# BatteryMonitor.net
KiCad netlist of a schematic drawn in Altium Designer
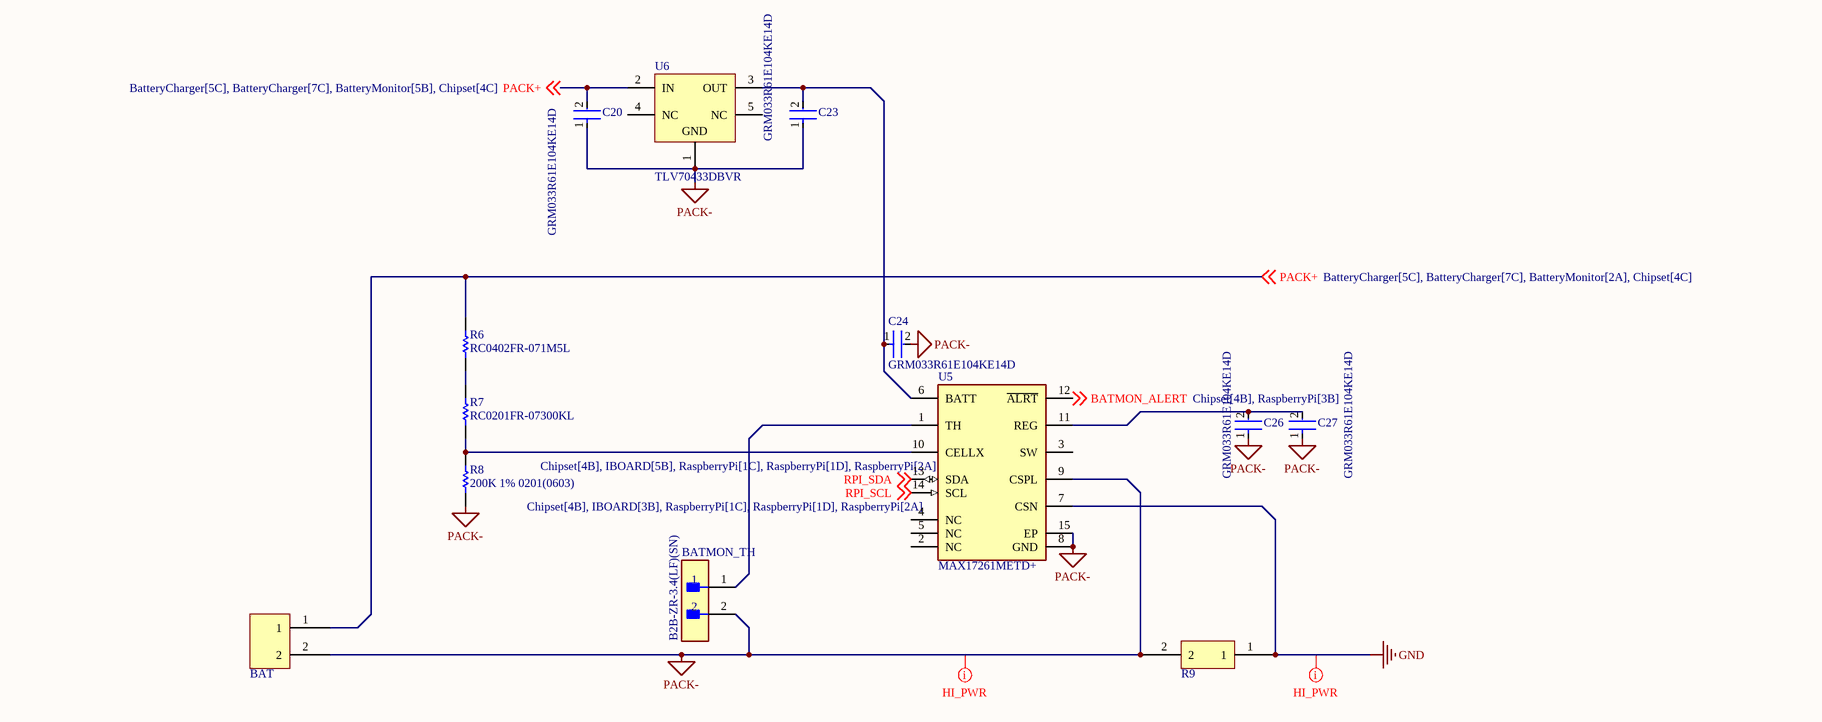
[diagram p0: BatteryMonitor.SchDoc]

(export (version "E")
  (design (tool "Eeschema 10.0.6"))
  (components
    (comp (ref "BAT")
      (value "WJ500V-5.08-2P")
      (footprint "WJ500V-5.08-2P")
      (libsource (lib "WJ500V-5.08-2P") (part "WJ500V-5.08-2P"))
    )
    (comp (ref "BATMON_TH")
      (value "B2B-ZR-3.4(LF)(SN)")
      (footprint "FP-B2B-ZR-3_4_LF_SN-MFG")
      (description "CONN HEADER VERT 2POS 1.5MM")
      (libsource (lib "Altium Content Vault") (part "3bc925449376181038e59eaffc5286c"))
    )
    (comp (ref "C20")
      (value "GRM033R61E104KE14D")
      (footprint "FP-GRM033-0_03-IPC_B")
      (description "Chip Multilayer Ceramic Capacitors for General Purpose, 0201, 0.10uF, X5R, 15%, 10%, 25V")
      (fields (field (name "TOLERANCE") "10%"))
      (libsource (lib "Altium Content Vault") (part "b4654b650e69147ec39a6b967a45e02"))
    )
    (comp (ref "C23")
      (value "GRM033R61E104KE14D")
      (footprint "FP-GRM033-0_03-IPC_B")
      (description "Chip Multilayer Ceramic Capacitors for General Purpose, 0201, 0.10uF, X5R, 15%, 10%, 25V")
      (fields (field (name "TOLERANCE") "10%"))
      (libsource (lib "Altium Content Vault") (part "b4654b650e69147ec39a6b967a45e02"))
    )
    (comp (ref "C24")
      (value "GRM033R61E104KE14D")
      (footprint "FP-GRM033-0_03-IPC_B")
      (description "Chip Multilayer Ceramic Capacitors for General Purpose, 0201, 0.10uF, X5R, 15%, 10%, 25V")
      (fields (field (name "TOLERANCE") "10%"))
      (libsource (lib "Altium Content Vault") (part "b4654b650e69147ec39a6b967a45e02"))
    )
    (comp (ref "C26")
      (value "GRM033R61E104KE14D")
      (footprint "FP-GRM033-0_03-IPC_B")
      (description "Chip Multilayer Ceramic Capacitors for General Purpose, 0201, 0.10uF, X5R, 15%, 10%, 25V")
      (fields (field (name "TOLERANCE") "10%"))
      (libsource (lib "Altium Content Vault") (part "b4654b650e69147ec39a6b967a45e02"))
    )
    (comp (ref "C27")
      (value "GRM033R61E104KE14D")
      (footprint "FP-GRM033-0_03-IPC_B")
      (description "Chip Multilayer Ceramic Capacitors for General Purpose, 0201, 0.10uF, X5R, 15%, 10%, 25V")
      (fields (field (name "TOLERANCE") "10%"))
      (libsource (lib "Altium Content Vault") (part "b4654b650e69147ec39a6b967a45e02"))
    )
    (comp (ref "R6")
      (value "RC0402FR-071M5L")
      (footprint "RESC1005X40X25NL05T10")
      (fields (field (name "MANUFACTURER") "Yageo / Phycomp"))
      (libsource (lib "Altium Content Vault") (part "RES"))
    )
    (comp (ref "R7")
      (value "RC0201FR-07300KL")
      (footprint "RESC0201(0603)_L")
      (description "300K 0.05W 1% 0201 (0603 Metric)  SMD")
      (fields (field (name "POWER") "0.05 W") (field (name "TOLERANCE") "1 %"))
      (libsource (lib "Altium Content Vault") (part "RES"))
    )
    (comp (ref "R8")
      (value "200K 1% 0201(0603)")
      (footprint "RESC0201(0603)_N")
      (description "200K 0.05W 1% 0201 (0603 Metric)  SMD")
      (fields (field (name "TOLERANCE") "1 %") (field (name "POWER") "0.05 W"))
      (libsource (lib "Altium Content Vault") (part "RES"))
    )
    (comp (ref "R9")
      (value "HoYLR2512-3W-10mR-1%")
      (footprint "HoYLR2512-3W-10mR-1%")
      (libsource (lib "HoYLR2512-3W-10mR-1%") (part "HoYLR2512-3W-10mR-1%"))
    )
    (comp (ref "U5")
      (value "MAX17261METD+")
      (footprint "FP-T1433-2C-MFG")
      (description "IC FUEL GAUGE LI+ M5 EZ 14TDFN")
      (fields
        (field (name "OCTOPART") "https://octopart.com/max17261metd%2B-maxim+integrated-91765041")
        (field (name "MANUFACTURER") "Maxim")
      )
      (libsource (lib "Altium Content Vault") (part "6a95d388af7a6271f6af8175f327b7b"))
    )
    (comp (ref "U6")
      (value "TLV70433DBVR")
      (footprint "DBV0005A_M")
      (fields (field (name "MANUFACTURER") "Texas Instruments"))
      (libsource (lib "Altium Content Vault") (part "TI-TLV704XXDBV5"))
    )
  )
  (nets
    (net (code "1") (name "BATMON_ALERT") (class "Default")
      (node (ref "U5") (pin "12") (pinfunction "~{ALRT}_12") (pintype "open_collector"))
    )
    (net (code "2") (name "GND") (class "Default")
      (node (ref "R9") (pin "1") (pinfunction "1_1") (pintype "passive"))
      (node (ref "U5") (pin "7") (pinfunction "CSN_7") (pintype "passive"))
    )
    (net (code "3") (name "Net-(R6-Pad1)") (class "Default")
      (node (ref "R6") (pin "1") (pinfunction "1_1") (pintype "passive"))
      (node (ref "R7") (pin "2") (pinfunction "2_2") (pintype "passive"))
    )
    (net (code "4") (name "Net-(U5-BATT)") (class "Default")
      (node (ref "C23") (pin "2") (pinfunction "2_2") (pintype "passive"))
      (node (ref "C24") (pin "1") (pinfunction "1_1") (pintype "passive"))
      (node (ref "U5") (pin "6") (pinfunction "BATT_6") (pintype "power_in"))
      (node (ref "U6") (pin "3") (pinfunction "OUT_3") (pintype "power_in"))
    )
    (net (code "5") (name "Net-(U5-CELLX)") (class "Default")
      (node (ref "R7") (pin "1") (pinfunction "1_1") (pintype "passive"))
      (node (ref "R8") (pin "2") (pinfunction "2_2") (pintype "passive"))
      (node (ref "U5") (pin "10") (pinfunction "CELLX_10") (pintype "passive"))
    )
    (net (code "6") (name "Net-(U5-REG)") (class "Default")
      (node (ref "C26") (pin "2") (pinfunction "2_2") (pintype "passive"))
      (node (ref "C27") (pin "2") (pinfunction "2_2") (pintype "passive"))
      (node (ref "U5") (pin "11") (pinfunction "REG_11") (pintype "power_in"))
    )
    (net (code "7") (name "Net-(U5-TH)") (class "Default")
      (node (ref "BATMON_TH") (pin "1") (pinfunction "1_1") (pintype "passive"))
      (node (ref "U5") (pin "1") (pinfunction "TH_1") (pintype "passive"))
    )
    (net (code "8") (name "PACK+") (class "Default")
      (node (ref "BAT") (pin "1") (pinfunction "1_1") (pintype "passive"))
      (node (ref "C20") (pin "2") (pinfunction "2_2") (pintype "passive"))
      (node (ref "R6") (pin "2") (pinfunction "2_2") (pintype "passive"))
      (node (ref "U6") (pin "2") (pinfunction "IN_2") (pintype "power_in"))
    )
    (net (code "9") (name "PACK-") (class "Default")
      (node (ref "BAT") (pin "2") (pinfunction "2_2") (pintype "passive"))
      (node (ref "BATMON_TH") (pin "2") (pinfunction "2_2") (pintype "passive"))
      (node (ref "C20") (pin "1") (pinfunction "1_1") (pintype "passive"))
      (node (ref "C23") (pin "1") (pinfunction "1_1") (pintype "passive"))
      (node (ref "C24") (pin "2") (pinfunction "2_2") (pintype "passive"))
      (node (ref "C26") (pin "1") (pinfunction "1_1") (pintype "passive"))
      (node (ref "C27") (pin "1") (pinfunction "1_1") (pintype "passive"))
      (node (ref "R8") (pin "1") (pinfunction "1_1") (pintype "passive"))
      (node (ref "R9") (pin "2") (pinfunction "2_2") (pintype "passive"))
      (node (ref "U5") (pin "15") (pinfunction "EP_15") (pintype "power_in"))
      (node (ref "U5") (pin "8") (pinfunction "GND_8") (pintype "power_in"))
      (node (ref "U5") (pin "9") (pinfunction "CSPL_9") (pintype "passive"))
      (node (ref "U6") (pin "1") (pinfunction "GND_1") (pintype "power_in"))
    )
    (net (code "10") (name "RPI_SCL") (class "Default")
      (node (ref "U5") (pin "14") (pinfunction "SCL_14") (pintype "input"))
    )
    (net (code "11") (name "RPI_SDA") (class "Default")
      (node (ref "U5") (pin "13") (pinfunction "SDA_13") (pintype "bidirectional"))
    )
    (net (code "12") (name "unconnected-(U5-NC-Pad2)") (class "Default")
      (node (ref "U5") (pin "2") (pinfunction "NC_2") (pintype "passive"))
    )
    (net (code "13") (name "unconnected-(U5-NC-Pad4)") (class "Default")
      (node (ref "U5") (pin "4") (pinfunction "NC_4") (pintype "passive"))
    )
    (net (code "14") (name "unconnected-(U5-NC-Pad5)") (class "Default")
      (node (ref "U5") (pin "5") (pinfunction "NC_5") (pintype "passive"))
    )
    (net (code "15") (name "unconnected-(U5-SW-Pad3)") (class "Default")
      (node (ref "U5") (pin "3") (pinfunction "SW_3") (pintype "passive"))
    )
    (net (code "16") (name "unconnected-(U6-NC-Pad4)") (class "Default")
      (node (ref "U6") (pin "4") (pinfunction "NC_4") (pintype "passive"))
    )
    (net (code "17") (name "unconnected-(U6-NC-Pad5)") (class "Default")
      (node (ref "U6") (pin "5") (pinfunction "NC_5") (pintype "passive"))
    )
  )
)
